# Side_PCB.net
KiCad netlist of a schematic drawn in Altium Designer
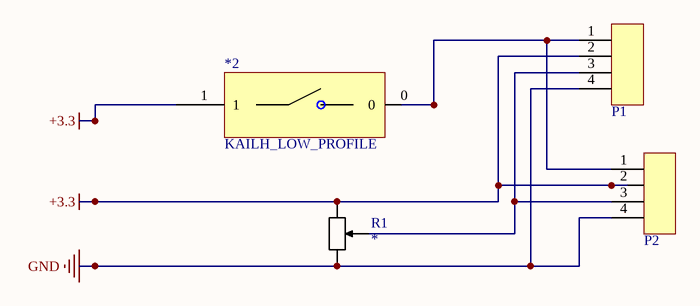
[diagram p0: Side PCB.SchDoc]

(export (version "E")
  (design (tool "Eeschema 10.0.6"))
  (components
    (comp (ref "*2")
      (value "KAILH_LOW_PROFILE")
      (footprint "KAILH_LOW_PROFILE")
      (libsource (lib "FF_component_lib") (part "KAILH_LOW_PROFILE"))
    )
    (comp (ref "P1")
      (value "JST_SE_4PIN")
      (footprint "JST_SE_4PIN")
      (libsource (lib "FF_component_lib") (part "JST_SE_4PIN"))
    )
    (comp (ref "P2")
      (value "JST_SE_4PIN")
      (footprint "JST_SE_4PIN")
      (libsource (lib "FF_component_lib") (part "JST_SE_4PIN"))
    )
    (comp (ref "R1")
      (value "R_POTMETER")
      (fields (field (name "ALTIUM_VALUE") "*"))
      (libsource (lib "FF_component_lib") (part "R_POTMETER"))
    )
  )
  (nets
    (net (code "1") (name "+3.3") (class "Default")
      (node (ref "*2") (pin "1") (pinfunction "1_1") (pintype "passive"))
      (node (ref "P1") (pin "2") (pinfunction "2_2") (pintype "passive"))
      (node (ref "P2") (pin "2") (pinfunction "2_2") (pintype "passive"))
      (node (ref "R1") (pin "1") (pinfunction "1_1") (pintype "passive"))
    )
    (net (code "2") (name "GND") (class "Default")
      (node (ref "P1") (pin "4") (pinfunction "4_4") (pintype "passive"))
      (node (ref "P2") (pin "4") (pinfunction "4_4") (pintype "passive"))
      (node (ref "R1") (pin "2") (pinfunction "2_2") (pintype "passive"))
    )
    (net (code "3") (name "Net-(*2-Pad0)") (class "Default")
      (node (ref "*2") (pin "0") (pinfunction "0_0") (pintype "passive"))
      (node (ref "P1") (pin "1") (pinfunction "1_1") (pintype "passive"))
      (node (ref "P2") (pin "1") (pinfunction "1_1") (pintype "passive"))
    )
    (net (code "4") (name "Net-(P1-Pad3)") (class "Default")
      (node (ref "P1") (pin "3") (pinfunction "3_3") (pintype "passive"))
      (node (ref "P2") (pin "3") (pinfunction "3_3") (pintype "passive"))
    )
  )
)
